# Lamp_Gcse_Main_Control_board_V0_3.net
KiCad netlist of a schematic drawn in EasyEDA Pro
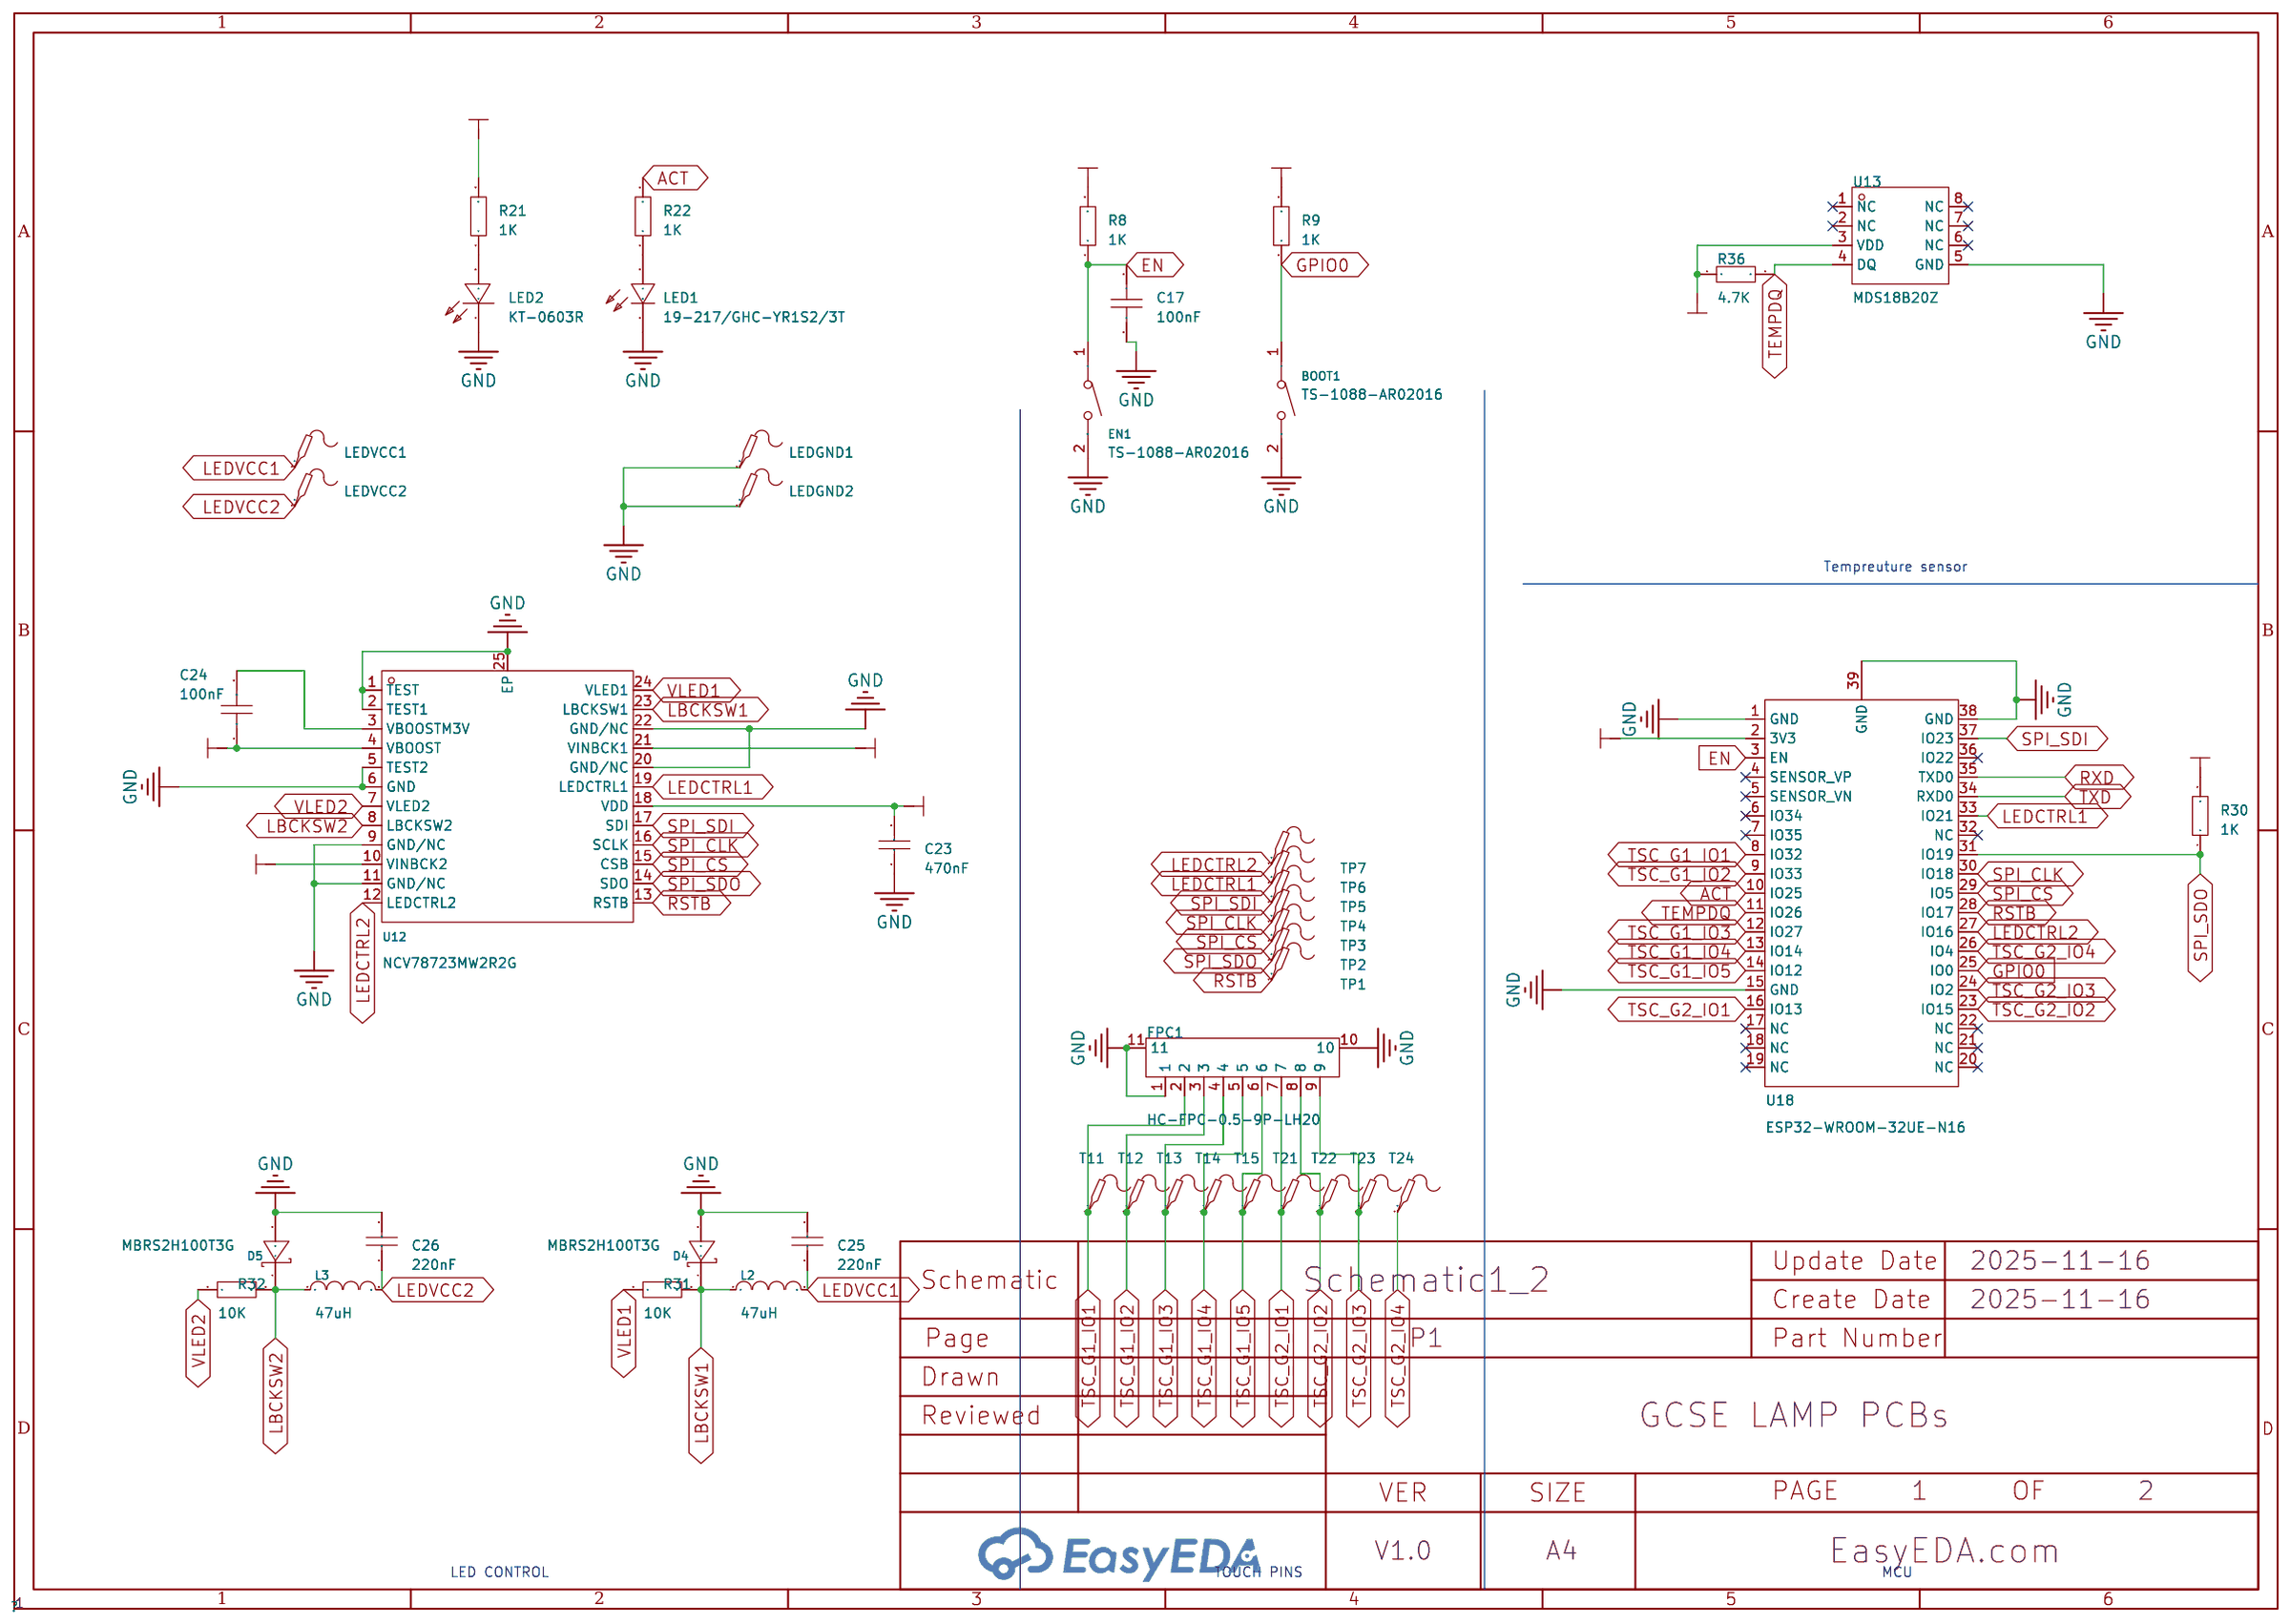
[diagram p0: P1]
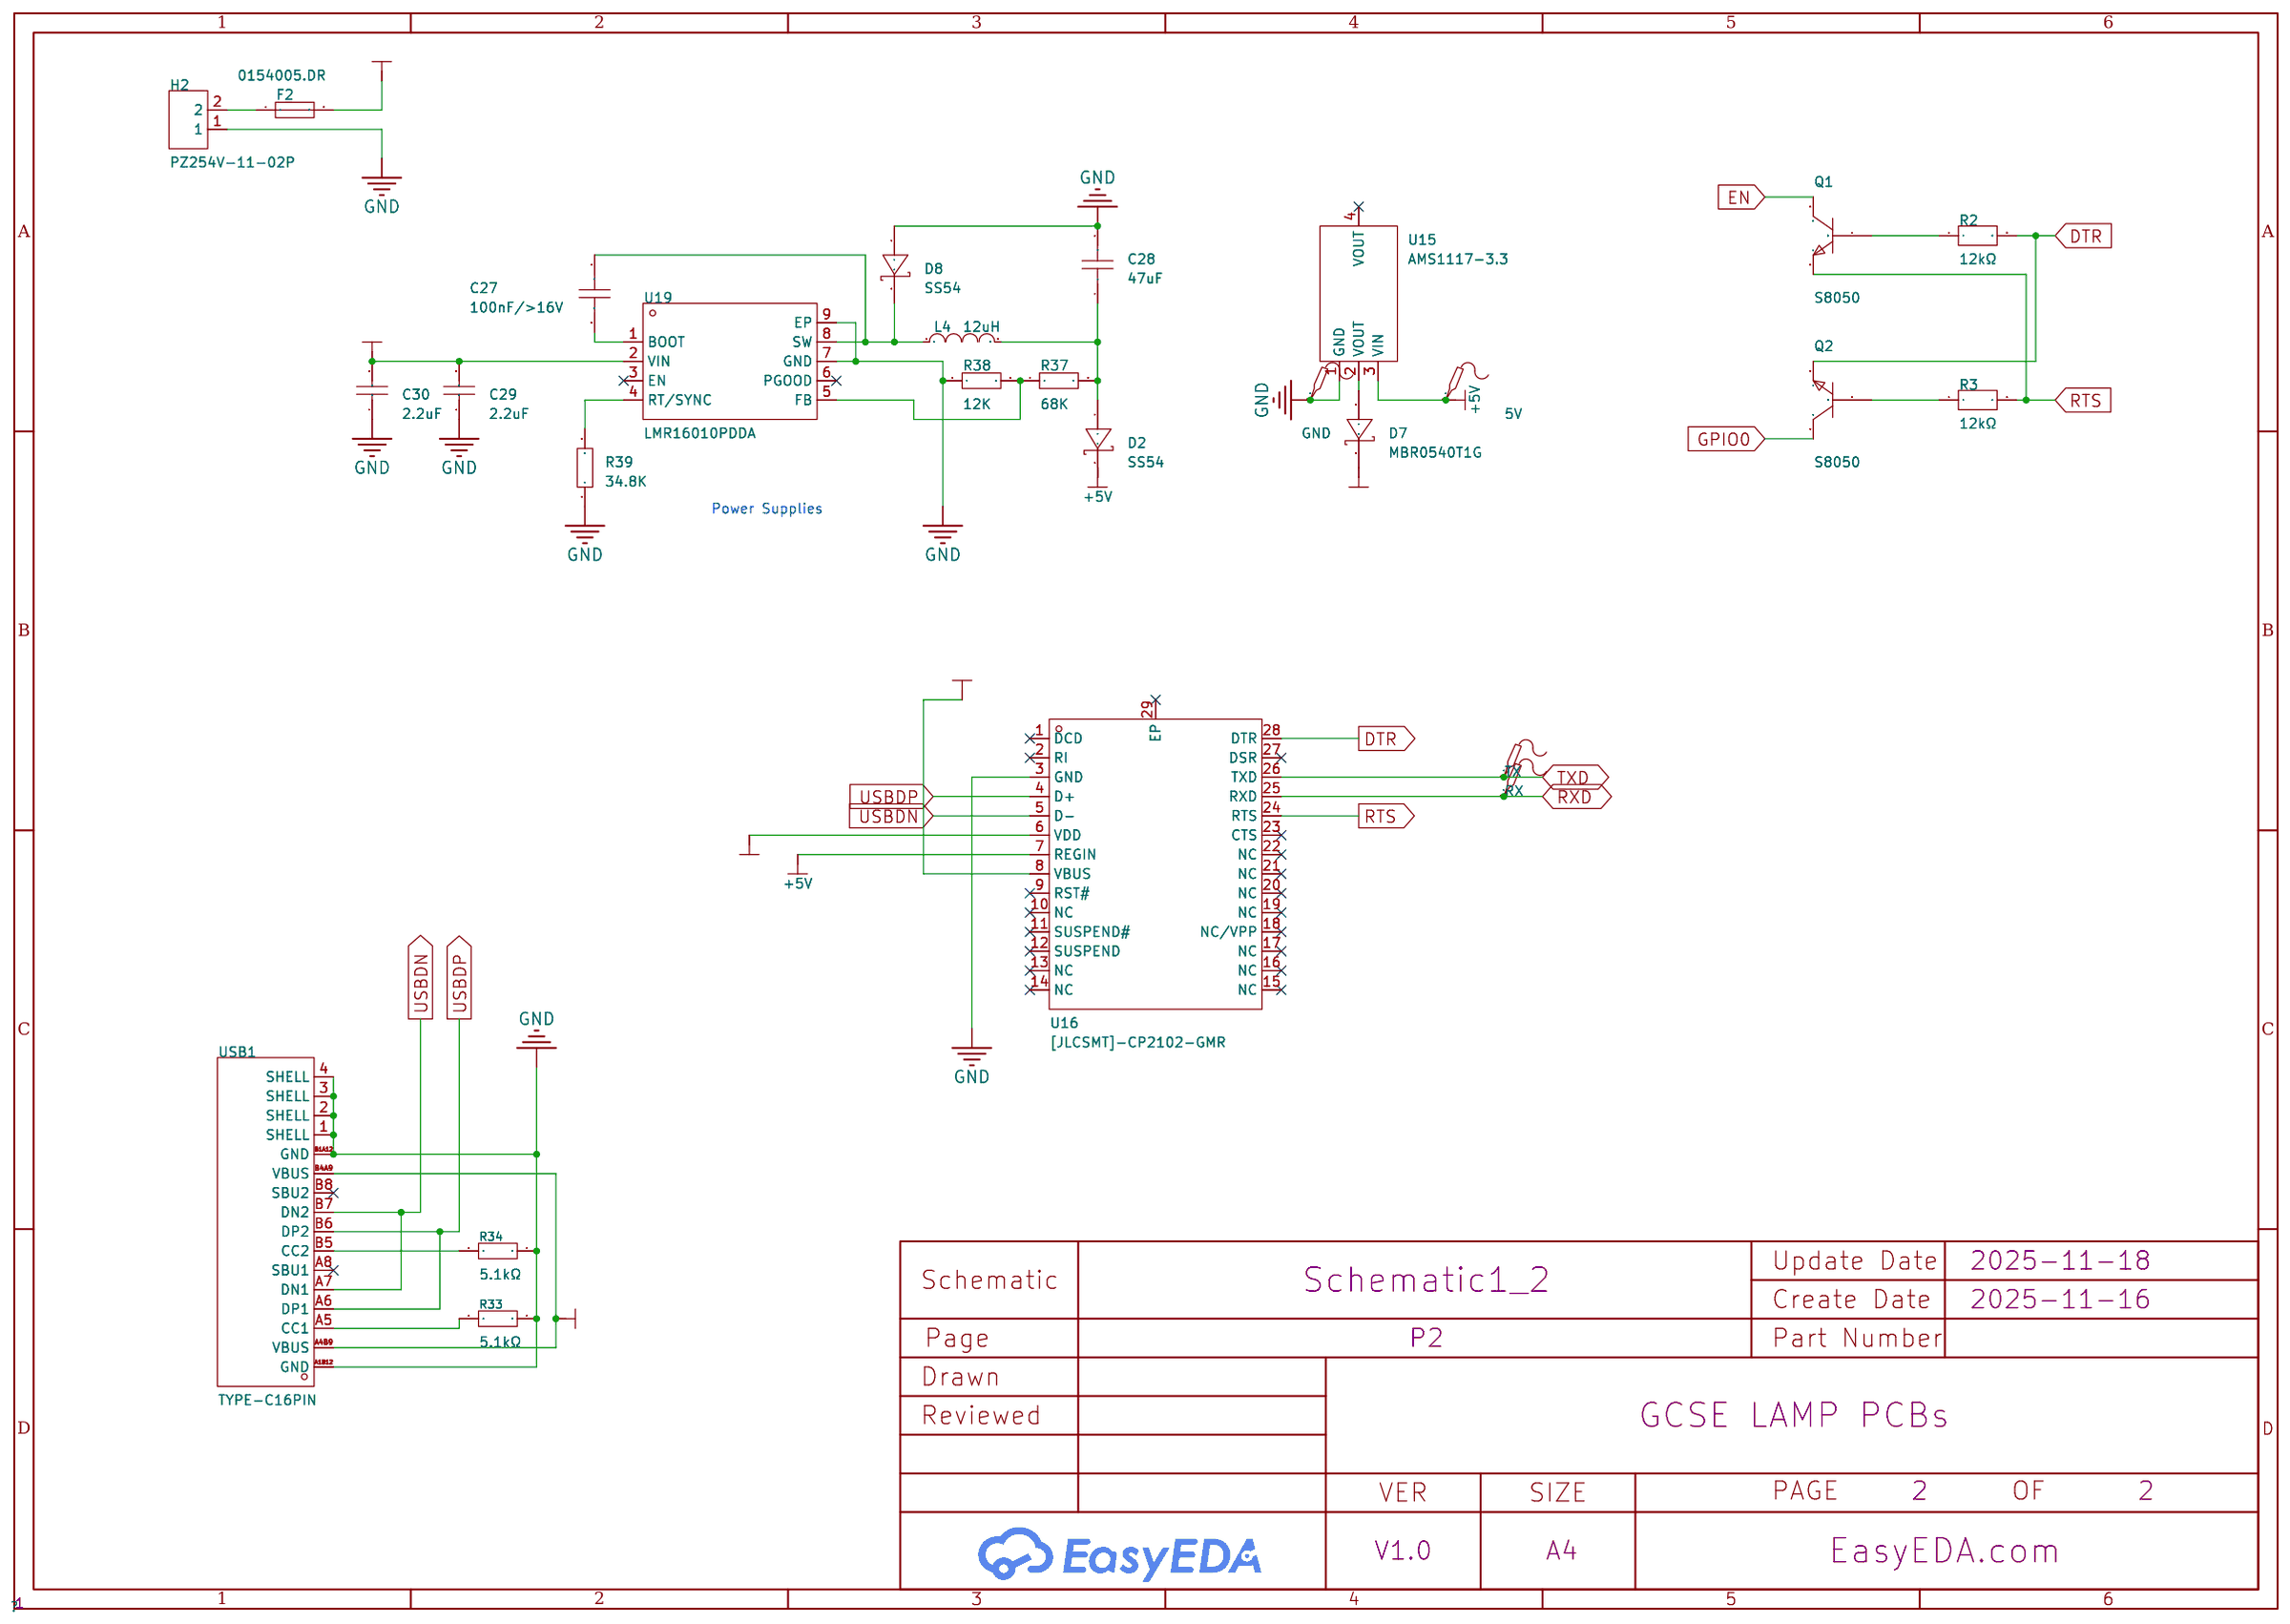
[diagram p1: P2]

(export (version "E")
  (design (tool "Eeschema 10.0.6"))
  (components
    (comp (ref "BOOT1")
      (value "TS-1088-AR02016")
      (footprint "easyedapro:SW-SMD_L3.9-W3.0-P4.45")
      (fields (field (name "Manufacturer") "XUNPU(讯普)"))
      (libsource (lib "easyedapro") (part "TS-1088-AR02016"))
    )
    (comp (ref "C17")
      (value "100nF")
      (footprint "easyedapro:C0603")
      (description "Capacitance:0.1uF Tolerance:±10% Tolerance:±10% Voltage Rating:50V Temperature Coefficient:X7R")
      (fields (field (name "Manufacturer Part") "GMC10X7R104K50NT") (field (name "Manufacturer") "CAL-CHIP"))
      (libsource (lib "easyedapro") (part "CAP"))
    )
    (comp (ref "C23")
      (value "470nF")
      (footprint "easyedapro:C0603")
      (fields
        (field (name "Manufacturer Part") "CL10B474KA8NNNC")
        (field (name "Manufacturer") "SAMSUNG(三星)")
      )
      (libsource (lib "easyedapro") (part "CL10B474KA8NNNC"))
    )
    (comp (ref "C24")
      (value "100nF")
      (footprint "easyedapro:C0805")
      (fields
        (field (name "Manufacturer Part") "CC0805KRX7R9BB104")
        (field (name "Manufacturer") "YAGEO(国巨)")
      )
      (libsource (lib "easyedapro") (part "CC0805KRX7R9BB104"))
    )
    (comp (ref "C25")
      (value "220nF")
      (footprint "easyedapro:C0603")
      (fields
        (field (name "Manufacturer Part") "CL10B224KB8NNNC")
        (field (name "Manufacturer") "SAMSUNG(三星)")
      )
      (libsource (lib "easyedapro") (part "CL10B224KB8NNNC"))
    )
    (comp (ref "C26")
      (value "220nF")
      (footprint "easyedapro:C0603")
      (fields
        (field (name "Manufacturer Part") "CL10B224KB8NNNC")
        (field (name "Manufacturer") "SAMSUNG(三星)")
      )
      (libsource (lib "easyedapro") (part "CL10B224KB8NNNC"))
    )
    (comp (ref "D4")
      (value "MBRS2H100T3G")
      (footprint "easyedapro:SMB_L4.6-W3.6-LS5.3-RD")
      (fields (field (name "Manufacturer") "onsemi(安森美)"))
      (libsource (lib "easyedapro") (part "MBRS2H100T3G"))
    )
    (comp (ref "D5")
      (value "MBRS2H100T3G")
      (footprint "easyedapro:SMB_L4.6-W3.6-LS5.3-RD")
      (fields (field (name "Manufacturer") "onsemi(安森美)"))
      (libsource (lib "easyedapro") (part "MBRS2H100T3G"))
    )
    (comp (ref "EN1")
      (value "TS-1088-AR02016")
      (footprint "easyedapro:SW-SMD_L3.9-W3.0-P4.45")
      (fields (field (name "Manufacturer") "XUNPU(讯普)"))
      (libsource (lib "easyedapro") (part "TS-1088-AR02016"))
    )
    (comp (ref "FPC1")
      (value "HC-FPC-0.5-9P-LH20")
      (footprint "easyedapro:FPC-SMD_9P-P0.50_HC-FPC-0.5-9P-LH20")
      (fields (field (name "Manufacturer") "HC(虹成电子)"))
      (libsource (lib "easyedapro") (part "HC-FPC-0.5-9P-LH20"))
    )
    (comp (ref "L2")
      (value "47uH")
      (footprint "easyedapro:IND-SMD_L11.5-W10.0_SMMS1040")
      (fields (field (name "Manufacturer Part") "SMMS1040-470M") (field (name "Manufacturer") "SXN(顺翔诺)"))
      (libsource (lib "easyedapro") (part "SMMS1040-470M"))
    )
    (comp (ref "L3")
      (value "47uH")
      (footprint "easyedapro:IND-SMD_L11.5-W10.0_SMMS1040")
      (fields (field (name "Manufacturer Part") "SMMS1040-470M") (field (name "Manufacturer") "SXN(顺翔诺)"))
      (libsource (lib "easyedapro") (part "SMMS1040-470M"))
    )
    (comp (ref "LED1")
      (value "19-217/GHC-YR1S2/3T")
      (footprint "easyedapro:LED0603-RD")
      (fields (field (name "Manufacturer") "EVERLIGHT(亿光)"))
      (libsource (lib "easyedapro") (part "19-217/GHC-YR1S2/3T"))
    )
    (comp (ref "LED2")
      (value "KT-0603R")
      (footprint "easyedapro:LED0603-RD")
      (fields (field (name "Manufacturer") "KENTO"))
      (libsource (lib "easyedapro") (part "KT-0603R"))
    )
    (comp (ref "LEDGND1")
      (value "~")
      (footprint "easyedapro:Test-Point-0.5mm")
      (description "Test Point 测试点")
      (libsource (lib "easyedapro") (part "Test-Point"))
    )
    (comp (ref "LEDGND2")
      (value "~")
      (footprint "easyedapro:Test-Point-0.5mm")
      (description "Test Point 测试点")
      (libsource (lib "easyedapro") (part "Test-Point"))
    )
    (comp (ref "LEDVCC1")
      (value "~")
      (footprint "easyedapro:Test-Point-0.5mm")
      (description "Test Point 测试点")
      (libsource (lib "easyedapro") (part "Test-Point"))
    )
    (comp (ref "LEDVCC2")
      (value "~")
      (footprint "easyedapro:Test-Point-0.5mm")
      (description "Test Point 测试点")
      (libsource (lib "easyedapro") (part "Test-Point"))
    )
    (comp (ref "R8") (value "1K") (footprint "easyedapro:R0603") (libsource (lib "easyedapro") (part "Res")))
    (comp (ref "R9") (value "1K") (footprint "easyedapro:R0603") (libsource (lib "easyedapro") (part "Res")))
    (comp (ref "R21") (value "1K") (libsource (lib "easyedapro") (part "Res")))
    (comp (ref "R22") (value "1K") (libsource (lib "easyedapro") (part "Res")))
    (comp (ref "R30") (value "1K") (footprint "easyedapro:R0603") (libsource (lib "easyedapro") (part "Res")))
    (comp (ref "R31")
      (value "10K")
      (footprint "easyedapro:R0603")
      (libsource (lib "easyedapro") (part "Res"))
    )
    (comp (ref "R32")
      (value "10K")
      (footprint "easyedapro:R0603")
      (libsource (lib "easyedapro") (part "Res"))
    )
    (comp (ref "R36")
      (value "4.7K")
      (footprint "easyedapro:R0603")
      (libsource (lib "easyedapro") (part "Res"))
    )
    (comp (ref "T11")
      (value "~")
      (footprint "easyedapro:Test-Point-0.5mm")
      (description "Test Point 测试点")
      (libsource (lib "easyedapro") (part "Test-Point"))
    )
    (comp (ref "T12")
      (value "~")
      (footprint "easyedapro:Test-Point-0.5mm")
      (description "Test Point 测试点")
      (libsource (lib "easyedapro") (part "Test-Point"))
    )
    (comp (ref "T13")
      (value "~")
      (footprint "easyedapro:Test-Point-0.5mm")
      (description "Test Point 测试点")
      (libsource (lib "easyedapro") (part "Test-Point"))
    )
    (comp (ref "T14")
      (value "~")
      (footprint "easyedapro:Test-Point-0.5mm")
      (description "Test Point 测试点")
      (libsource (lib "easyedapro") (part "Test-Point"))
    )
    (comp (ref "T15")
      (value "~")
      (footprint "easyedapro:Test-Point-0.5mm")
      (description "Test Point 测试点")
      (libsource (lib "easyedapro") (part "Test-Point"))
    )
    (comp (ref "T21")
      (value "~")
      (footprint "easyedapro:Test-Point-0.5mm")
      (description "Test Point 测试点")
      (libsource (lib "easyedapro") (part "Test-Point"))
    )
    (comp (ref "T22")
      (value "~")
      (footprint "easyedapro:Test-Point-0.5mm")
      (description "Test Point 测试点")
      (libsource (lib "easyedapro") (part "Test-Point"))
    )
    (comp (ref "T23")
      (value "~")
      (footprint "easyedapro:Test-Point-0.5mm")
      (description "Test Point 测试点")
      (libsource (lib "easyedapro") (part "Test-Point"))
    )
    (comp (ref "T24")
      (value "~")
      (footprint "easyedapro:Test-Point-0.5mm")
      (description "Test Point 测试点")
      (libsource (lib "easyedapro") (part "Test-Point"))
    )
    (comp (ref "TP1")
      (value "~")
      (footprint "easyedapro:Test-Point-0.5mm")
      (description "Test Point 测试点")
      (libsource (lib "easyedapro") (part "Test-Point"))
    )
    (comp (ref "TP2")
      (value "~")
      (footprint "easyedapro:Test-Point-0.5mm")
      (description "Test Point 测试点")
      (libsource (lib "easyedapro") (part "Test-Point"))
    )
    (comp (ref "TP3")
      (value "~")
      (footprint "easyedapro:Test-Point-0.5mm")
      (description "Test Point 测试点")
      (libsource (lib "easyedapro") (part "Test-Point"))
    )
    (comp (ref "TP4")
      (value "~")
      (footprint "easyedapro:Test-Point-0.5mm")
      (description "Test Point 测试点")
      (libsource (lib "easyedapro") (part "Test-Point"))
    )
    (comp (ref "TP5")
      (value "~")
      (footprint "easyedapro:Test-Point-0.5mm")
      (description "Test Point 测试点")
      (libsource (lib "easyedapro") (part "Test-Point"))
    )
    (comp (ref "TP6")
      (value "~")
      (footprint "easyedapro:Test-Point-0.5mm")
      (description "Test Point 测试点")
      (libsource (lib "easyedapro") (part "Test-Point"))
    )
    (comp (ref "TP7")
      (value "~")
      (footprint "easyedapro:Test-Point-0.5mm")
      (description "Test Point 测试点")
      (libsource (lib "easyedapro") (part "Test-Point"))
    )
    (comp (ref "U12")
      (value "NCV78723MW2R2G")
      (footprint "easyedapro:QFN-24_L5.0-W5.0-P0.65-TL-EP3.5")
      (fields (field (name "Manufacturer") "onsemi(安森美)"))
      (libsource (lib "easyedapro") (part "NCV78723MW2R2G"))
    )
    (comp (ref "U13")
      (value "MDS18B20Z")
      (footprint "easyedapro:SOIC-8_L4.9-W3.9-P1.27-LS6.0-BL")
      (fields (field (name "Manufacturer") "MSKSEMI(美森科)"))
      (libsource (lib "easyedapro") (part "MDS18B20Z"))
    )
    (comp (ref "U18")
      (value "ESP32-WROOM-32UE-N16")
      (footprint "easyedapro:COMM-SMD_ESP32-WROOM-32UE-N16")
      (fields (field (name "Manufacturer") "ESPRESSIF(乐鑫)"))
      (libsource (lib "easyedapro") (part "ESP32-WROOM-32UE(16MB)"))
    )
    (comp (ref "5V")
      (value "~")
      (footprint "easyedapro:Test-Point-0.5mm")
      (description "Test Point 测试点")
      (libsource (lib "easyedapro") (part "Test-Point"))
    )
    (comp (ref "C27")
      (value "100nF/>16V")
      (footprint "easyedapro:C0603")
      (libsource (lib "easyedapro") (part "CAP"))
    )
    (comp (ref "C28")
      (value "47uF")
      (description "Capacitance:47uF Tolerance:±10% Tolerance:±10% Voltage Rating:16V Temperature Coefficient:X7R")
      (fields
        (field (name "Manufacturer Part") "CS3225X7R476K160NRL")
        (field (name "Manufacturer") "SAMWHA(三和)")
      )
      (libsource (lib "easyedapro") (part "CS3225X7R476K160NRL"))
    )
    (comp (ref "C29")
      (value "2.2uF")
      (footprint "easyedapro:C1210")
      (description "Capacitance:2.2uF Tolerance:±10% Tolerance:±10% Voltage Rating:100V Temperature Coefficient:X7R")
      (fields
        (field (name "Manufacturer Part") "CL32B225KCJSNNE")
        (field (name "Manufacturer") "SAMSUNG(三星)")
      )
      (libsource (lib "easyedapro") (part "CL32B225KCJSNNE"))
    )
    (comp (ref "C30")
      (value "2.2uF")
      (footprint "easyedapro:C1210")
      (description "Capacitance:2.2uF Tolerance:±10% Tolerance:±10% Voltage Rating:100V Temperature Coefficient:X7R")
      (fields
        (field (name "Manufacturer Part") "CL32B225KCJSNNE")
        (field (name "Manufacturer") "SAMSUNG(三星)")
      )
      (libsource (lib "easyedapro") (part "CL32B225KCJSNNE"))
    )
    (comp (ref "D2")
      (value "SS54")
      (footprint "easyedapro:SMA_L4.4-W2.8-LS5.4-R-RD")
      (fields (field (name "Manufacturer") "MDD(辰达半导体)"))
      (libsource (lib "easyedapro") (part "SS54_C22452"))
    )
    (comp (ref "D7")
      (value "MBR0540T1G")
      (footprint "easyedapro:SOD-123_L2.8-W1.8-LS3.7-RD")
      (fields (field (name "Manufacturer") "onsemi(安森美)"))
      (libsource (lib "easyedapro") (part "MBR0540T1G"))
    )
    (comp (ref "D8")
      (value "SS54")
      (footprint "easyedapro:SMA_L4.4-W2.8-LS5.4-R-RD")
      (fields (field (name "Manufacturer") "MDD(辰达半导体)"))
      (libsource (lib "easyedapro") (part "SS54_C22452"))
    )
    (comp (ref "F2")
      (value "0154005.DR")
      (footprint "easyedapro:FUSE-SMD_L9.8-W5.1")
      (fields (field (name "Manufacturer") "Littelfuse(美国力特)"))
      (libsource (lib "easyedapro") (part "0154005.DR"))
    )
    (comp (ref "GND")
      (value "~")
      (footprint "easyedapro:Test-Point-0.5mm")
      (description "Test Point 测试点")
      (libsource (lib "easyedapro") (part "Test-Point"))
    )
    (comp (ref "H2")
      (value "PZ254V-11-02P")
      (footprint "easyedapro:HDR-TH_2P-P2.54-V-M")
      (fields (field (name "Manufacturer") "XFCN(兴飞)"))
      (libsource (lib "easyedapro") (part "PZ254V-11-02P"))
    )
    (comp (ref "L4")
      (value "12uH")
      (footprint "easyedapro:IND-SMD_L4.0-W4.0_FNR40XXS")
      (fields (field (name "Manufacturer Part") "FNR4030S120MT") (field (name "Manufacturer") "cjiang(长江微电)"))
      (libsource (lib "easyedapro") (part "FNR4030S120MT"))
    )
    (comp (ref "Q1")
      (value "S8050")
      (footprint "easyedapro:SOT-23-3_L2.9-W1.3-P1.90-LS2.4-BR")
      (libsource (lib "easyedapro") (part "S8050_C139514"))
    )
    (comp (ref "Q2")
      (value "S8050")
      (footprint "easyedapro:SOT-23-3_L2.9-W1.3-P1.90-LS2.4-BR")
      (libsource (lib "easyedapro") (part "S8050_C139514"))
    )
    (comp (ref "R2")
      (value "12kΩ")
      (footprint "easyedapro:R0805")
      (fields (field (name "Manufacturer Part") "RT0805BRE0712KL") (field (name "Manufacturer") "YAGEO(国巨)"))
      (libsource (lib "easyedapro") (part "RT0805BRE0712KL"))
    )
    (comp (ref "R3")
      (value "12kΩ")
      (footprint "easyedapro:R0805")
      (fields (field (name "Manufacturer Part") "RT0805BRE0712KL") (field (name "Manufacturer") "YAGEO(国巨)"))
      (libsource (lib "easyedapro") (part "RT0805BRE0712KL"))
    )
    (comp (ref "R33")
      (value "5.1kΩ")
      (footprint "easyedapro:R0805")
      (fields (field (name "Manufacturer Part") "RMC08055.1K1%N") (field (name "Manufacturer") "Tyohm(幸亚电阻)"))
      (libsource (lib "easyedapro") (part "RMC08055.1K1%N"))
    )
    (comp (ref "R34")
      (value "5.1kΩ")
      (footprint "easyedapro:R0805")
      (fields (field (name "Manufacturer Part") "RMC08055.1K1%N") (field (name "Manufacturer") "Tyohm(幸亚电阻)"))
      (libsource (lib "easyedapro") (part "RMC08055.1K1%N"))
    )
    (comp (ref "R37")
      (value "68K")
      (footprint "easyedapro:R0603")
      (libsource (lib "easyedapro") (part "Res"))
    )
    (comp (ref "R38")
      (value "12K")
      (footprint "easyedapro:R0603")
      (libsource (lib "easyedapro") (part "Res"))
    )
    (comp (ref "R39")
      (value "34.8K")
      (footprint "easyedapro:R0603")
      (libsource (lib "easyedapro") (part "Res"))
    )
    (comp (ref "RX")
      (value "~")
      (footprint "easyedapro:Test-Point-0.5mm")
      (description "Test Point 测试点")
      (libsource (lib "easyedapro") (part "Test-Point"))
    )
    (comp (ref "TX")
      (value "~")
      (footprint "easyedapro:Test-Point-0.5mm")
      (description "Test Point 测试点")
      (libsource (lib "easyedapro") (part "Test-Point"))
    )
    (comp (ref "U15")
      (value "AMS1117-3.3")
      (footprint "easyedapro:SOT-223-3_L6.5-W3.4-P2.30-LS7.0-BR")
      (fields (field (name "Manufacturer") "AMS"))
      (libsource (lib "easyedapro") (part "AMS1117-3.3"))
    )
    (comp (ref "U16")
      (value "[JLCSMT]-CP2102-GMR")
      (footprint "easyedapro:QFN-28_L5.0-W5.0-P0.50-BL-EP3.15")
      (libsource (lib "easyedapro") (part "[JLCSMT]-CP2102-GMR"))
    )
    (comp (ref "U19")
      (value "LMR16010PDDA")
      (footprint "easyedapro:SO-8_L4.9-W3.9-P1.27-LS6.0-BL-EP")
      (fields (field (name "Manufacturer") "TI(德州仪器)"))
      (libsource (lib "easyedapro") (part "LMR16010PDDA"))
    )
    (comp (ref "USB1")
      (value "TYPE-C16PIN")
      (footprint "easyedapro:USB-C-SMD_TYPE-C16PIN")
      (fields (field (name "Manufacturer") "SHOU HAN(首韩)"))
      (libsource (lib "easyedapro") (part "TYPE-C16PIN"))
    )
  )
  (nets
    (net (code "1") (name "+3.3V") (class "Default")
      (node (ref "C23") (pin "2") (pinfunction "2_2") (pintype "input"))
      (node (ref "D7") (pin "1") (pinfunction "K_1") (pintype "unspecified"))
      (node (ref "R21") (pin "2") (pinfunction "2_2") (pintype "input"))
      (node (ref "R30") (pin "2") (pinfunction "2_2") (pintype "input"))
      (node (ref "R36") (pin "1") (pinfunction "1_1") (pintype "input"))
      (node (ref "R8") (pin "2") (pinfunction "2_2") (pintype "input"))
      (node (ref "R9") (pin "2") (pinfunction "2_2") (pintype "input"))
      (node (ref "U12") (pin "18") (pinfunction "VDD_18") (pintype "input"))
      (node (ref "U13") (pin "3") (pinfunction "VDD_3") (pintype "unspecified"))
      (node (ref "U16") (pin "6") (pinfunction "VDD_6") (pintype "input"))
      (node (ref "U18") (pin "2") (pinfunction "3V3_2") (pintype "unspecified"))
    )
    (net (code "2") (name "+5V") (class "Default")
      (node (ref "5V") (pin "1") (pinfunction "1_1") (pintype "unspecified"))
      (node (ref "D2") (pin "2") (pinfunction "K_2") (pintype "unspecified"))
      (node (ref "U15") (pin "3") (pinfunction "VIN_3") (pintype "unspecified"))
      (node (ref "U16") (pin "7") (pinfunction "REGIN_7") (pintype "input"))
      (node (ref "U16") (pin "8") (pinfunction "VBUS_8") (pintype "input"))
      (node (ref "USB1") (pin "A4B9") (pinfunction "VBUS_A4B9") (pintype "unspecified"))
      (node (ref "USB1") (pin "B4A9") (pinfunction "VBUS_B4A9") (pintype "unspecified"))
    )
    (net (code "3") (name "24VIN") (class "Default")
      (node (ref "C24") (pin "1") (pinfunction "1_1") (pintype "unspecified"))
      (node (ref "C29") (pin "2") (pinfunction "2_2") (pintype "input"))
      (node (ref "C30") (pin "2") (pinfunction "2_2") (pintype "input"))
      (node (ref "F2") (pin "2") (pinfunction "2_2") (pintype "unspecified"))
      (node (ref "U12") (pin "10") (pinfunction "VINBCK2_10") (pintype "input"))
      (node (ref "U12") (pin "21") (pinfunction "VINBCK1_21") (pintype "input"))
      (node (ref "U12") (pin "4") (pinfunction "VBOOST_4") (pintype "input"))
      (node (ref "U19") (pin "2") (pinfunction "VIN_2") (pintype "unspecified"))
    )
    (net (code "4") (name "ACT") (class "Default")
      (node (ref "R22") (pin "2") (pinfunction "2_2") (pintype "input"))
      (node (ref "U18") (pin "10") (pinfunction "IO25_10") (pintype "unspecified"))
    )
    (net (code "5") (name "DTR") (class "Default")
      (node (ref "Q2") (pin "2") (pinfunction "E_2") (pintype "input"))
      (node (ref "R2") (pin "2") (pinfunction "2_2") (pintype "unspecified"))
      (node (ref "U16") (pin "28") (pinfunction "DTR_28") (pintype "input"))
    )
    (net (code "6") (name "EN") (class "Default")
      (node (ref "C17") (pin "1") (pinfunction "1_1") (pintype "input"))
      (node (ref "EN1") (pin "1") (pinfunction "1_1") (pintype "input"))
      (node (ref "Q1") (pin "3") (pinfunction "C_3") (pintype "input"))
      (node (ref "R8") (pin "1") (pinfunction "1_1") (pintype "input"))
      (node (ref "U18") (pin "3") (pinfunction "EN_3") (pintype "unspecified"))
    )
    (net (code "7") (name "GND") (class "Default")
      (node (ref "BOOT1") (pin "2") (pinfunction "2_2") (pintype "input"))
      (node (ref "C17") (pin "2") (pinfunction "2_2") (pintype "input"))
      (node (ref "C23") (pin "1") (pinfunction "1_1") (pintype "input"))
      (node (ref "C25") (pin "2") (pinfunction "2_2") (pintype "input"))
      (node (ref "C26") (pin "2") (pinfunction "2_2") (pintype "input"))
      (node (ref "C28") (pin "2") (pinfunction "2_2") (pintype "unspecified"))
      (node (ref "C29") (pin "1") (pinfunction "1_1") (pintype "input"))
      (node (ref "C30") (pin "1") (pinfunction "1_1") (pintype "input"))
      (node (ref "D4") (pin "2") (pinfunction "A_2") (pintype "input"))
      (node (ref "D5") (pin "2") (pinfunction "A_2") (pintype "input"))
      (node (ref "D8") (pin "1") (pinfunction "A_1") (pintype "unspecified"))
      (node (ref "EN1") (pin "2") (pinfunction "2_2") (pintype "input"))
      (node (ref "FPC1") (pin "1") (pinfunction "1_1") (pintype "unspecified"))
      (node (ref "FPC1") (pin "10") (pinfunction "10_10") (pintype "unspecified"))
      (node (ref "FPC1") (pin "11") (pinfunction "11_11") (pintype "unspecified"))
      (node (ref "GND") (pin "1") (pinfunction "1_1") (pintype "unspecified"))
      (node (ref "H2") (pin "1") (pinfunction "1_1") (pintype "unspecified"))
      (node (ref "LED1") (pin "1") (pinfunction "C_1") (pintype "input"))
      (node (ref "LED2") (pin "1") (pinfunction "K_1") (pintype "unspecified"))
      (node (ref "LEDGND1") (pin "1") (pinfunction "1_1") (pintype "unspecified"))
      (node (ref "LEDGND2") (pin "1") (pinfunction "1_1") (pintype "unspecified"))
      (node (ref "R33") (pin "1") (pinfunction "1_1") (pintype "input"))
      (node (ref "R34") (pin "1") (pinfunction "1_1") (pintype "input"))
      (node (ref "R38") (pin "1") (pinfunction "1_1") (pintype "input"))
      (node (ref "R39") (pin "1") (pinfunction "1_1") (pintype "input"))
      (node (ref "U12") (pin "1") (pinfunction "TEST_1") (pintype "input"))
      (node (ref "U12") (pin "11") (pinfunction "GND/NC_11") (pintype "input"))
      (node (ref "U12") (pin "2") (pinfunction "TEST1_2") (pintype "input"))
      (node (ref "U12") (pin "20") (pinfunction "GND/NC_20") (pintype "input"))
      (node (ref "U12") (pin "22") (pinfunction "GND/NC_22") (pintype "input"))
      (node (ref "U12") (pin "25") (pinfunction "EP_25") (pintype "input"))
      (node (ref "U12") (pin "5") (pinfunction "TEST2_5") (pintype "input"))
      (node (ref "U12") (pin "6") (pinfunction "GND_6") (pintype "input"))
      (node (ref "U12") (pin "9") (pinfunction "GND/NC_9") (pintype "input"))
      (node (ref "U13") (pin "5") (pinfunction "GND_5") (pintype "unspecified"))
      (node (ref "U15") (pin "1") (pinfunction "GND_1") (pintype "unspecified"))
      (node (ref "U16") (pin "3") (pinfunction "GND_3") (pintype "input"))
      (node (ref "U18") (pin "1") (pinfunction "GND_1") (pintype "unspecified"))
      (node (ref "U18") (pin "15") (pinfunction "GND_15") (pintype "unspecified"))
      (node (ref "U18") (pin "38") (pinfunction "GND_38") (pintype "unspecified"))
      (node (ref "U18") (pin "39") (pinfunction "GND_39") (pintype "unspecified"))
      (node (ref "U19") (pin "7") (pinfunction "GND_7") (pintype "unspecified"))
      (node (ref "U19") (pin "9") (pinfunction "EP_9") (pintype "unspecified"))
      (node (ref "USB1") (pin "1") (pinfunction "SHELL_1") (pintype "unspecified"))
      (node (ref "USB1") (pin "2") (pinfunction "SHELL_2") (pintype "unspecified"))
      (node (ref "USB1") (pin "3") (pinfunction "SHELL_3") (pintype "unspecified"))
      (node (ref "USB1") (pin "4") (pinfunction "SHELL_4") (pintype "unspecified"))
      (node (ref "USB1") (pin "A1B12") (pinfunction "GND_A1B12") (pintype "unspecified"))
      (node (ref "USB1") (pin "B1A12") (pinfunction "GND_B1A12") (pintype "unspecified"))
    )
    (net (code "8") (name "GPIO0") (class "Default")
      (node (ref "BOOT1") (pin "1") (pinfunction "1_1") (pintype "input"))
      (node (ref "Q2") (pin "3") (pinfunction "C_3") (pintype "input"))
      (node (ref "R9") (pin "1") (pinfunction "1_1") (pintype "input"))
      (node (ref "U18") (pin "25") (pinfunction "IO0_25") (pintype "unspecified"))
    )
    (net (code "9") (name "LBCKSW1") (class "Default")
      (node (ref "D4") (pin "1") (pinfunction "K_1") (pintype "input"))
      (node (ref "L2") (pin "1") (pinfunction "1_1") (pintype "input"))
      (node (ref "R31") (pin "2") (pinfunction "2_2") (pintype "input"))
      (node (ref "U12") (pin "23") (pinfunction "LBCKSW1_23") (pintype "input"))
    )
    (net (code "10") (name "LBCKSW2") (class "Default")
      (node (ref "D5") (pin "1") (pinfunction "K_1") (pintype "input"))
      (node (ref "L3") (pin "1") (pinfunction "1_1") (pintype "input"))
      (node (ref "R32") (pin "2") (pinfunction "2_2") (pintype "input"))
      (node (ref "U12") (pin "8") (pinfunction "LBCKSW2_8") (pintype "input"))
    )
    (net (code "11") (name "LEDCTRL1") (class "Default")
      (node (ref "TP6") (pin "1") (pinfunction "1_1") (pintype "unspecified"))
      (node (ref "U12") (pin "19") (pinfunction "LEDCTRL1_19") (pintype "input"))
      (node (ref "U18") (pin "33") (pinfunction "IO21_33") (pintype "unspecified"))
    )
    (net (code "12") (name "LEDCTRL2") (class "Default")
      (node (ref "TP7") (pin "1") (pinfunction "1_1") (pintype "unspecified"))
      (node (ref "U12") (pin "12") (pinfunction "LEDCTRL2_12") (pintype "input"))
      (node (ref "U18") (pin "27") (pinfunction "IO16_27") (pintype "unspecified"))
    )
    (net (code "13") (name "LEDVCC1") (class "Default")
      (node (ref "C25") (pin "1") (pinfunction "1_1") (pintype "input"))
      (node (ref "L2") (pin "2") (pinfunction "2_2") (pintype "input"))
      (node (ref "LEDVCC1") (pin "1") (pinfunction "1_1") (pintype "unspecified"))
    )
    (net (code "14") (name "LEDVCC2") (class "Default")
      (node (ref "C26") (pin "1") (pinfunction "1_1") (pintype "input"))
      (node (ref "L3") (pin "2") (pinfunction "2_2") (pintype "input"))
      (node (ref "LEDVCC2") (pin "1") (pinfunction "1_1") (pintype "unspecified"))
    )
    (net (code "15") (name "Net-(D2-A)") (class "Default")
      (node (ref "C28") (pin "1") (pinfunction "1_1") (pintype "unspecified"))
      (node (ref "D2") (pin "1") (pinfunction "A_1") (pintype "unspecified"))
      (node (ref "L4") (pin "2") (pinfunction "2_2") (pintype "unspecified"))
      (node (ref "R37") (pin "2") (pinfunction "2_2") (pintype "input"))
    )
    (net (code "16") (name "Net-(D7-A)") (class "Default")
      (node (ref "D7") (pin "2") (pinfunction "A_2") (pintype "unspecified"))
      (node (ref "U15") (pin "2") (pinfunction "VOUT_2") (pintype "unspecified"))
    )
    (net (code "17") (name "Net-(D8-K)") (class "Default")
      (node (ref "C27") (pin "1") (pinfunction "1_1") (pintype "input"))
      (node (ref "D8") (pin "2") (pinfunction "K_2") (pintype "unspecified"))
      (node (ref "L4") (pin "1") (pinfunction "1_1") (pintype "unspecified"))
      (node (ref "U19") (pin "8") (pinfunction "SW_8") (pintype "unspecified"))
    )
    (net (code "18") (name "Net-(F2-Pad1)") (class "Default")
      (node (ref "F2") (pin "1") (pinfunction "1_1") (pintype "unspecified"))
      (node (ref "H2") (pin "2") (pinfunction "2_2") (pintype "unspecified"))
    )
    (net (code "19") (name "Net-(LED1-A)") (class "Default")
      (node (ref "LED1") (pin "2") (pinfunction "A_2") (pintype "input"))
      (node (ref "R22") (pin "1") (pinfunction "1_1") (pintype "input"))
    )
    (net (code "20") (name "Net-(LED2-A)") (class "Default")
      (node (ref "LED2") (pin "2") (pinfunction "A_2") (pintype "unspecified"))
      (node (ref "R21") (pin "1") (pinfunction "1_1") (pintype "input"))
    )
    (net (code "21") (name "Net-(Q1-B)") (class "Default")
      (node (ref "Q1") (pin "1") (pinfunction "B_1") (pintype "input"))
      (node (ref "R2") (pin "1") (pinfunction "1_1") (pintype "unspecified"))
    )
    (net (code "22") (name "Net-(Q2-B)") (class "Default")
      (node (ref "Q2") (pin "1") (pinfunction "B_1") (pintype "input"))
      (node (ref "R3") (pin "1") (pinfunction "1_1") (pintype "unspecified"))
    )
    (net (code "23") (name "Net-(U12-VBOOSTM3V)") (class "Default")
      (node (ref "C24") (pin "2") (pinfunction "2_2") (pintype "unspecified"))
      (node (ref "U12") (pin "3") (pinfunction "VBOOSTM3V_3") (pintype "input"))
    )
    (net (code "24") (name "Net-(U19-BOOT)") (class "Default")
      (node (ref "C27") (pin "2") (pinfunction "2_2") (pintype "input"))
      (node (ref "U19") (pin "1") (pinfunction "BOOT_1") (pintype "unspecified"))
    )
    (net (code "25") (name "Net-(U19-FB)") (class "Default")
      (node (ref "R37") (pin "1") (pinfunction "1_1") (pintype "input"))
      (node (ref "R38") (pin "2") (pinfunction "2_2") (pintype "input"))
      (node (ref "U19") (pin "5") (pinfunction "FB_5") (pintype "unspecified"))
    )
    (net (code "26") (name "Net-(U19-RT{slash}SYNC)") (class "Default")
      (node (ref "R39") (pin "2") (pinfunction "2_2") (pintype "input"))
      (node (ref "U19") (pin "4") (pinfunction "RT/SYNC_4") (pintype "unspecified"))
    )
    (net (code "27") (name "Net-(USB1-CC1)") (class "Default")
      (node (ref "R33") (pin "2") (pinfunction "2_2") (pintype "input"))
      (node (ref "USB1") (pin "A5") (pinfunction "CC1_A5") (pintype "unspecified"))
    )
    (net (code "28") (name "Net-(USB1-CC2)") (class "Default")
      (node (ref "R34") (pin "2") (pinfunction "2_2") (pintype "input"))
      (node (ref "USB1") (pin "B5") (pinfunction "CC2_B5") (pintype "unspecified"))
    )
    (net (code "29") (name "RSTB") (class "Default")
      (node (ref "TP1") (pin "1") (pinfunction "1_1") (pintype "unspecified"))
      (node (ref "U12") (pin "13") (pinfunction "RSTB_13") (pintype "input"))
      (node (ref "U18") (pin "28") (pinfunction "IO17_28") (pintype "unspecified"))
    )
    (net (code "30") (name "RTS") (class "Default")
      (node (ref "Q1") (pin "2") (pinfunction "E_2") (pintype "input"))
      (node (ref "R3") (pin "2") (pinfunction "2_2") (pintype "unspecified"))
      (node (ref "U16") (pin "24") (pinfunction "RTS_24") (pintype "input"))
    )
    (net (code "31") (name "RXD") (class "Default")
      (node (ref "RX") (pin "1") (pinfunction "1_1") (pintype "unspecified"))
      (node (ref "U16") (pin "25") (pinfunction "RXD_25") (pintype "input"))
      (node (ref "U18") (pin "35") (pinfunction "TXD0_35") (pintype "unspecified"))
    )
    (net (code "32") (name "SPI_CLK") (class "Default")
      (node (ref "TP4") (pin "1") (pinfunction "1_1") (pintype "unspecified"))
      (node (ref "U12") (pin "16") (pinfunction "SCLK_16") (pintype "input"))
      (node (ref "U18") (pin "30") (pinfunction "IO18_30") (pintype "unspecified"))
    )
    (net (code "33") (name "SPI_CS") (class "Default")
      (node (ref "TP3") (pin "1") (pinfunction "1_1") (pintype "unspecified"))
      (node (ref "U12") (pin "15") (pinfunction "CSB_15") (pintype "input"))
      (node (ref "U18") (pin "29") (pinfunction "IO5_29") (pintype "unspecified"))
    )
    (net (code "34") (name "SPI_SDI") (class "Default")
      (node (ref "TP5") (pin "1") (pinfunction "1_1") (pintype "unspecified"))
      (node (ref "U12") (pin "17") (pinfunction "SDI_17") (pintype "input"))
      (node (ref "U18") (pin "37") (pinfunction "IO23_37") (pintype "unspecified"))
    )
    (net (code "35") (name "SPI_SDO") (class "Default")
      (node (ref "R30") (pin "1") (pinfunction "1_1") (pintype "input"))
      (node (ref "TP2") (pin "1") (pinfunction "1_1") (pintype "unspecified"))
      (node (ref "U12") (pin "14") (pinfunction "SDO_14") (pintype "input"))
      (node (ref "U18") (pin "31") (pinfunction "IO19_31") (pintype "unspecified"))
    )
    (net (code "36") (name "TEMPDQ") (class "Default")
      (node (ref "R36") (pin "2") (pinfunction "2_2") (pintype "input"))
      (node (ref "U13") (pin "4") (pinfunction "DQ_4") (pintype "unspecified"))
      (node (ref "U18") (pin "11") (pinfunction "IO26_11") (pintype "unspecified"))
    )
    (net (code "37") (name "TSC_G1_IO1") (class "Default")
      (node (ref "FPC1") (pin "2") (pinfunction "2_2") (pintype "unspecified"))
      (node (ref "T11") (pin "1") (pinfunction "1_1") (pintype "unspecified"))
      (node (ref "U18") (pin "8") (pinfunction "IO32_8") (pintype "unspecified"))
    )
    (net (code "38") (name "TSC_G1_IO2") (class "Default")
      (node (ref "FPC1") (pin "3") (pinfunction "3_3") (pintype "unspecified"))
      (node (ref "T12") (pin "1") (pinfunction "1_1") (pintype "unspecified"))
      (node (ref "U18") (pin "9") (pinfunction "IO33_9") (pintype "unspecified"))
    )
    (net (code "39") (name "TSC_G1_IO3") (class "Default")
      (node (ref "FPC1") (pin "4") (pinfunction "4_4") (pintype "unspecified"))
      (node (ref "T13") (pin "1") (pinfunction "1_1") (pintype "unspecified"))
      (node (ref "U18") (pin "12") (pinfunction "IO27_12") (pintype "unspecified"))
    )
    (net (code "40") (name "TSC_G1_IO4") (class "Default")
      (node (ref "FPC1") (pin "5") (pinfunction "5_5") (pintype "unspecified"))
      (node (ref "T14") (pin "1") (pinfunction "1_1") (pintype "unspecified"))
      (node (ref "U18") (pin "13") (pinfunction "IO14_13") (pintype "unspecified"))
    )
    (net (code "41") (name "TSC_G1_IO5") (class "Default")
      (node (ref "FPC1") (pin "6") (pinfunction "6_6") (pintype "unspecified"))
      (node (ref "T15") (pin "1") (pinfunction "1_1") (pintype "unspecified"))
      (node (ref "U18") (pin "14") (pinfunction "IO12_14") (pintype "unspecified"))
    )
    (net (code "42") (name "TSC_G2_IO1") (class "Default")
      (node (ref "FPC1") (pin "7") (pinfunction "7_7") (pintype "unspecified"))
      (node (ref "T21") (pin "1") (pinfunction "1_1") (pintype "unspecified"))
      (node (ref "U18") (pin "16") (pinfunction "IO13_16") (pintype "unspecified"))
    )
    (net (code "43") (name "TSC_G2_IO2") (class "Default")
      (node (ref "FPC1") (pin "8") (pinfunction "8_8") (pintype "unspecified"))
      (node (ref "T22") (pin "1") (pinfunction "1_1") (pintype "unspecified"))
      (node (ref "U18") (pin "23") (pinfunction "IO15_23") (pintype "unspecified"))
    )
    (net (code "44") (name "TSC_G2_IO3") (class "Default")
      (node (ref "FPC1") (pin "9") (pinfunction "9_9") (pintype "unspecified"))
      (node (ref "T23") (pin "1") (pinfunction "1_1") (pintype "unspecified"))
      (node (ref "U18") (pin "24") (pinfunction "IO2_24") (pintype "unspecified"))
    )
    (net (code "45") (name "TSC_G2_IO4") (class "Default")
      (node (ref "T24") (pin "1") (pinfunction "1_1") (pintype "unspecified"))
      (node (ref "U18") (pin "26") (pinfunction "IO4_26") (pintype "unspecified"))
    )
    (net (code "46") (name "TXD") (class "Default")
      (node (ref "TX") (pin "1") (pinfunction "1_1") (pintype "unspecified"))
      (node (ref "U16") (pin "26") (pinfunction "TXD_26") (pintype "input"))
      (node (ref "U18") (pin "34") (pinfunction "RXD0_34") (pintype "unspecified"))
    )
    (net (code "47") (name "USBDN") (class "Default")
      (node (ref "U16") (pin "5") (pinfunction "D-_5") (pintype "input"))
      (node (ref "USB1") (pin "A7") (pinfunction "DN1_A7") (pintype "unspecified"))
      (node (ref "USB1") (pin "B7") (pinfunction "DN2_B7") (pintype "unspecified"))
    )
    (net (code "48") (name "USBDP") (class "Default")
      (node (ref "U16") (pin "4") (pinfunction "D+_4") (pintype "input"))
      (node (ref "USB1") (pin "A6") (pinfunction "DP1_A6") (pintype "unspecified"))
      (node (ref "USB1") (pin "B6") (pinfunction "DP2_B6") (pintype "unspecified"))
    )
    (net (code "49") (name "VLED1") (class "Default")
      (node (ref "R31") (pin "1") (pinfunction "1_1") (pintype "input"))
      (node (ref "U12") (pin "24") (pinfunction "VLED1_24") (pintype "input"))
    )
    (net (code "50") (name "VLED2") (class "Default")
      (node (ref "R32") (pin "1") (pinfunction "1_1") (pintype "input"))
      (node (ref "U12") (pin "7") (pinfunction "VLED2_7") (pintype "input"))
    )
    (net (code "51") (name "unconnected-(U13-NC-Pad1)") (class "Default")
      (node (ref "U13") (pin "1") (pinfunction "NC_1") (pintype "unspecified+no_connect"))
    )
    (net (code "52") (name "unconnected-(U13-NC-Pad2)") (class "Default")
      (node (ref "U13") (pin "2") (pinfunction "NC_2") (pintype "unspecified+no_connect"))
    )
    (net (code "53") (name "unconnected-(U13-NC-Pad6)") (class "Default")
      (node (ref "U13") (pin "6") (pinfunction "NC_6") (pintype "unspecified+no_connect"))
    )
    (net (code "54") (name "unconnected-(U13-NC-Pad7)") (class "Default")
      (node (ref "U13") (pin "7") (pinfunction "NC_7") (pintype "unspecified+no_connect"))
    )
    (net (code "55") (name "unconnected-(U13-NC-Pad8)") (class "Default")
      (node (ref "U13") (pin "8") (pinfunction "NC_8") (pintype "unspecified+no_connect"))
    )
    (net (code "56") (name "unconnected-(U15-VOUT-Pad4)") (class "Default")
      (node (ref "U15") (pin "4") (pinfunction "VOUT_4") (pintype "unspecified+no_connect"))
    )
    (net (code "57") (name "unconnected-(U16-CTS-Pad23)") (class "Default")
      (node (ref "U16") (pin "23") (pinfunction "CTS_23") (pintype "input+no_connect"))
    )
    (net (code "58") (name "unconnected-(U16-DCD-Pad1)") (class "Default")
      (node (ref "U16") (pin "1") (pinfunction "DCD_1") (pintype "input+no_connect"))
    )
    (net (code "59") (name "unconnected-(U16-DSR-Pad27)") (class "Default")
      (node (ref "U16") (pin "27") (pinfunction "DSR_27") (pintype "input+no_connect"))
    )
    (net (code "60") (name "unconnected-(U16-EP-Pad29)") (class "Default")
      (node (ref "U16") (pin "29") (pinfunction "EP_29") (pintype "input+no_connect"))
    )
    (net (code "61") (name "unconnected-(U16-NC-Pad10)") (class "Default")
      (node (ref "U16") (pin "10") (pinfunction "NC_10") (pintype "input+no_connect"))
    )
    (net (code "62") (name "unconnected-(U16-NC-Pad13)") (class "Default")
      (node (ref "U16") (pin "13") (pinfunction "NC_13") (pintype "input+no_connect"))
    )
    (net (code "63") (name "unconnected-(U16-NC-Pad14)") (class "Default")
      (node (ref "U16") (pin "14") (pinfunction "NC_14") (pintype "input+no_connect"))
    )
    (net (code "64") (name "unconnected-(U16-NC-Pad15)") (class "Default")
      (node (ref "U16") (pin "15") (pinfunction "NC_15") (pintype "input+no_connect"))
    )
    (net (code "65") (name "unconnected-(U16-NC-Pad16)") (class "Default")
      (node (ref "U16") (pin "16") (pinfunction "NC_16") (pintype "input+no_connect"))
    )
    (net (code "66") (name "unconnected-(U16-NC-Pad17)") (class "Default")
      (node (ref "U16") (pin "17") (pinfunction "NC_17") (pintype "input+no_connect"))
    )
    (net (code "67") (name "unconnected-(U16-NC-Pad19)") (class "Default")
      (node (ref "U16") (pin "19") (pinfunction "NC_19") (pintype "input+no_connect"))
    )
    (net (code "68") (name "unconnected-(U16-NC-Pad20)") (class "Default")
      (node (ref "U16") (pin "20") (pinfunction "NC_20") (pintype "input+no_connect"))
    )
    (net (code "69") (name "unconnected-(U16-NC-Pad21)") (class "Default")
      (node (ref "U16") (pin "21") (pinfunction "NC_21") (pintype "input+no_connect"))
    )
    (net (code "70") (name "unconnected-(U16-NC-Pad22)") (class "Default")
      (node (ref "U16") (pin "22") (pinfunction "NC_22") (pintype "input+no_connect"))
    )
    (net (code "71") (name "unconnected-(U16-NC{slash}VPP-Pad18)") (class "Default")
      (node (ref "U16") (pin "18") (pinfunction "NC/VPP_18") (pintype "input+no_connect"))
    )
    (net (code "72") (name "unconnected-(U16-RI-Pad2)") (class "Default")
      (node (ref "U16") (pin "2") (pinfunction "RI_2") (pintype "input+no_connect"))
    )
    (net (code "73") (name "unconnected-(U16-RST#-Pad9)") (class "Default")
      (node (ref "U16") (pin "9") (pinfunction "RST#_9") (pintype "input+no_connect"))
    )
    (net (code "74") (name "unconnected-(U16-SUSPEND#-Pad11)") (class "Default")
      (node (ref "U16") (pin "11") (pinfunction "SUSPEND#_11") (pintype "input+no_connect"))
    )
    (net (code "75") (name "unconnected-(U16-SUSPEND-Pad12)") (class "Default")
      (node (ref "U16") (pin "12") (pinfunction "SUSPEND_12") (pintype "input+no_connect"))
    )
    (net (code "76") (name "unconnected-(U18-IO22-Pad36)") (class "Default")
      (node (ref "U18") (pin "36") (pinfunction "IO22_36") (pintype "unspecified+no_connect"))
    )
    (net (code "77") (name "unconnected-(U18-IO34-Pad6)") (class "Default")
      (node (ref "U18") (pin "6") (pinfunction "IO34_6") (pintype "unspecified+no_connect"))
    )
    (net (code "78") (name "unconnected-(U18-IO35-Pad7)") (class "Default")
      (node (ref "U18") (pin "7") (pinfunction "IO35_7") (pintype "unspecified+no_connect"))
    )
    (net (code "79") (name "unconnected-(U18-NC-Pad17)") (class "Default")
      (node (ref "U18") (pin "17") (pinfunction "NC_17") (pintype "unspecified+no_connect"))
    )
    (net (code "80") (name "unconnected-(U18-NC-Pad18)") (class "Default")
      (node (ref "U18") (pin "18") (pinfunction "NC_18") (pintype "unspecified+no_connect"))
    )
    (net (code "81") (name "unconnected-(U18-NC-Pad19)") (class "Default")
      (node (ref "U18") (pin "19") (pinfunction "NC_19") (pintype "unspecified+no_connect"))
    )
    (net (code "82") (name "unconnected-(U18-NC-Pad20)") (class "Default")
      (node (ref "U18") (pin "20") (pinfunction "NC_20") (pintype "unspecified+no_connect"))
    )
    (net (code "83") (name "unconnected-(U18-NC-Pad21)") (class "Default")
      (node (ref "U18") (pin "21") (pinfunction "NC_21") (pintype "unspecified+no_connect"))
    )
    (net (code "84") (name "unconnected-(U18-NC-Pad22)") (class "Default")
      (node (ref "U18") (pin "22") (pinfunction "NC_22") (pintype "unspecified+no_connect"))
    )
    (net (code "85") (name "unconnected-(U18-NC-Pad32)") (class "Default")
      (node (ref "U18") (pin "32") (pinfunction "NC_32") (pintype "unspecified+no_connect"))
    )
    (net (code "86") (name "unconnected-(U18-SENSOR_VN-Pad5)") (class "Default")
      (node (ref "U18") (pin "5") (pinfunction "SENSOR_VN_5") (pintype "unspecified+no_connect"))
    )
    (net (code "87") (name "unconnected-(U18-SENSOR_VP-Pad4)") (class "Default")
      (node (ref "U18") (pin "4") (pinfunction "SENSOR_VP_4") (pintype "unspecified+no_connect"))
    )
    (net (code "88") (name "unconnected-(U19-EN-Pad3)") (class "Default")
      (node (ref "U19") (pin "3") (pinfunction "EN_3") (pintype "unspecified+no_connect"))
    )
    (net (code "89") (name "unconnected-(U19-PGOOD-Pad6)") (class "Default")
      (node (ref "U19") (pin "6") (pinfunction "PGOOD_6") (pintype "unspecified+no_connect"))
    )
    (net (code "90") (name "unconnected-(USB1-SBU1-PadA8)") (class "Default")
      (node (ref "USB1") (pin "A8") (pinfunction "SBU1_A8") (pintype "unspecified+no_connect"))
    )
    (net (code "91") (name "unconnected-(USB1-SBU2-PadB8)") (class "Default")
      (node (ref "USB1") (pin "B8") (pinfunction "SBU2_B8") (pintype "unspecified+no_connect"))
    )
  )
)
